# schematic.net
KiCad netlist of a schematic drawn in EAGLE
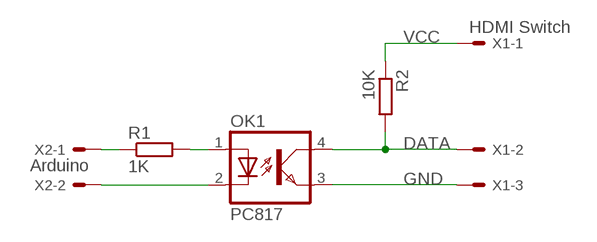
[diagram p0: schematic, sheet 1]

(export (version "E")
  (design (tool "Eeschema 10.0.6"))
  (components
    (comp (ref "OK1")
      (value "PC817")
      (footprint "eagle-import:DIL04")
      (fields (field (name "MPN") "PC817X4J000F"))
      (libsource (lib "eagle-import") (part "PC817"))
    )
    (comp (ref "R1")
      (value "1K")
      (footprint "eagle-import:0207_10")
      (libsource (lib "eagle-import") (part "R-EU_0207/10"))
    )
    (comp (ref "R2")
      (value "10K")
      (footprint "eagle-import:0207_10")
      (libsource (lib "eagle-import") (part "R-EU_0207/10"))
    )
    (comp (ref "X1")
      (value "HDMI Switch")
      (footprint "eagle-import:22-23-2031")
      (fields (field (name "MF") "MOLEX") (field (name "MPN") "22-23-2031"))
      (libsource (lib "eagle-import") (part "22-23-2031"))
    )
    (comp (ref "X2")
      (value "Arduino")
      (footprint "eagle-import:22-23-2021")
      (fields (field (name "MF") "MOLEX") (field (name "MPN") "22-23-2021"))
      (libsource (lib "eagle-import") (part "22-23-2021"))
    )
  )
  (nets
    (net (code "1") (name "/DATA") (class "Default")
      (node (ref "OK1") (pin "4") (pinfunction "COL_4") (pintype "passive"))
      (node (ref "R2") (pin "2") (pinfunction "2_2") (pintype "passive"))
      (node (ref "X1") (pin "2") (pinfunction "S_2") (pintype "passive"))
    )
    (net (code "2") (name "/GND") (class "Default")
      (node (ref "OK1") (pin "3") (pinfunction "EMIT_3") (pintype "passive"))
      (node (ref "X1") (pin "3") (pinfunction "S_3") (pintype "passive"))
    )
    (net (code "3") (name "/VCC") (class "Default")
      (node (ref "R2") (pin "1") (pinfunction "1_1") (pintype "passive"))
      (node (ref "X1") (pin "1") (pinfunction "S_1") (pintype "passive"))
    )
    (net (code "4") (name "Net-(OK1-A)") (class "Default")
      (node (ref "OK1") (pin "1") (pinfunction "A_1") (pintype "passive"))
      (node (ref "R1") (pin "2") (pinfunction "2_2") (pintype "passive"))
    )
    (net (code "5") (name "Net-(OK1-C)") (class "Default")
      (node (ref "OK1") (pin "2") (pinfunction "C_2") (pintype "passive"))
      (node (ref "X2") (pin "2") (pinfunction "S_2") (pintype "passive"))
    )
    (net (code "6") (name "Net-(X2A-S)") (class "Default")
      (node (ref "R1") (pin "1") (pinfunction "1_1") (pintype "passive"))
      (node (ref "X2") (pin "1") (pinfunction "S_1") (pintype "passive"))
    )
  )
)
